# MOSFET_driver.net
KiCad netlist of a schematic drawn in EAGLE
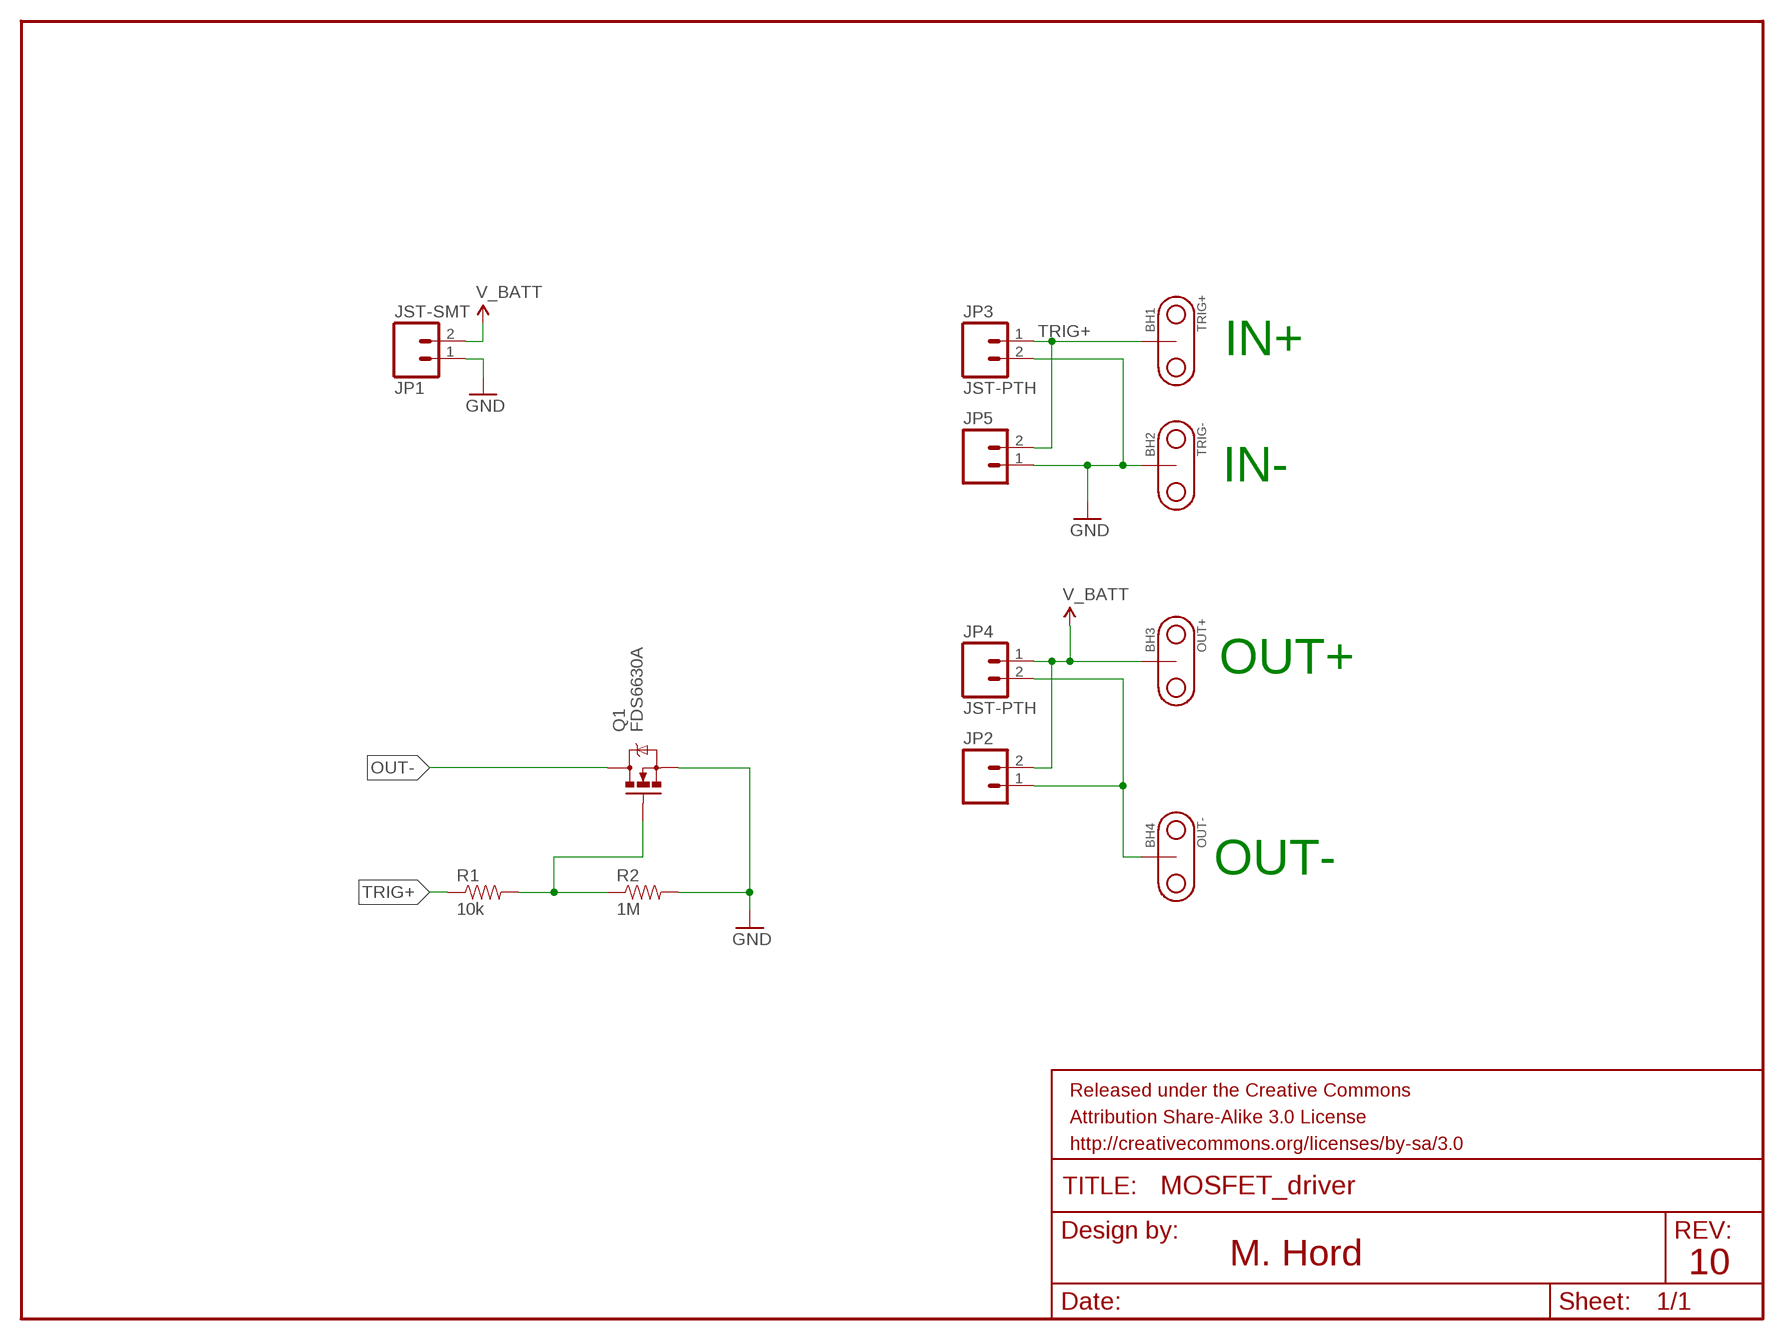
[diagram p0: schematic, sheet 1]

(export (version "E")
  (design (tool "Eeschema 10.0.6"))
  (components
    (comp (ref "BH1")
      (value "TRIG+")
      (footprint "eagle-import:BUTTONHOLE")
      (fields (field (name "NO_PART") "1"))
      (libsource (lib "eagle-import") (part "BUTTONHOLELARGE"))
    )
    (comp (ref "BH2")
      (value "TRIG-")
      (footprint "eagle-import:BUTTONHOLE")
      (fields (field (name "NO_PART") "1"))
      (libsource (lib "eagle-import") (part "BUTTONHOLELARGE"))
    )
    (comp (ref "BH3")
      (value "OUT+")
      (footprint "eagle-import:BUTTONHOLE")
      (fields (field (name "NO_PART") "1"))
      (libsource (lib "eagle-import") (part "BUTTONHOLELARGE"))
    )
    (comp (ref "BH4")
      (value "OUT-")
      (footprint "eagle-import:BUTTONHOLE")
      (fields (field (name "NO_PART") "1"))
      (libsource (lib "eagle-import") (part "BUTTONHOLELARGE"))
    )
    (comp (ref "FRAME1")
      (value "FRAME-LETTER")
      (footprint "eagle-import:CREATIVE_COMMONS")
      (libsource (lib "eagle-import") (part "FRAME-LETTER"))
    )
    (comp (ref "JP1")
      (value "JST-SMT")
      (footprint "eagle-import:JST-2-SMD")
      (fields (field (name "PROD_ID") "CONN-08352"))
      (libsource (lib "eagle-import") (part "M02-JST-2MM-SMT"))
    )
    (comp (ref "JP2")
      (value "M02PTH")
      (footprint "eagle-import:1X02")
      (libsource (lib "eagle-import") (part "M02PTH"))
    )
    (comp (ref "JP3")
      (value "JST-PTH")
      (footprint "eagle-import:JST-2-PTH-NS")
      (fields (field (name "NO_PART") "1"))
      (libsource (lib "eagle-import") (part "M02-JST-2-PTH-NO_SILK"))
    )
    (comp (ref "JP4")
      (value "JST-PTH")
      (footprint "eagle-import:JST-2-PTH-NS")
      (fields (field (name "NO_PART") "1"))
      (libsource (lib "eagle-import") (part "M02-JST-2-PTH-NO_SILK"))
    )
    (comp (ref "JP5")
      (value "M02PTH")
      (footprint "eagle-import:1X02")
      (libsource (lib "eagle-import") (part "M02PTH"))
    )
    (comp (ref "Q1")
      (value "FDS6630A")
      (footprint "eagle-import:SO08")
      (libsource (lib "eagle-import") (part "MOSFET-NCHANNELFDS6630A"))
    )
    (comp (ref "R1")
      (value "10k")
      (footprint "eagle-import:0402-RES")
      (libsource (lib "eagle-import") (part "RESISTOR0402-RES"))
    )
    (comp (ref "R2")
      (value "1M")
      (footprint "eagle-import:0402-RES")
      (libsource (lib "eagle-import") (part "1M-1%"))
    )
  )
  (nets
    (net (code "1") (name "GND") (class "Default")
      (node (ref "BH2") (pin "P$1") (pinfunction "P$1_P$1") (pintype "bidirectional"))
      (node (ref "JP1") (pin "1") (pinfunction "2_1") (pintype "passive"))
      (node (ref "JP3") (pin "2") (pinfunction "2_2") (pintype "passive"))
      (node (ref "JP5") (pin "1") (pinfunction "1_1") (pintype "passive"))
      (node (ref "Q1") (pin "1") (pinfunction "S_1") (pintype "passive"))
      (node (ref "Q1") (pin "2") (pinfunction "S_2") (pintype "passive"))
      (node (ref "Q1") (pin "3") (pinfunction "S_3") (pintype "passive"))
      (node (ref "R2") (pin "2") (pinfunction "2_2") (pintype "passive"))
    )
    (net (code "2") (name "Net-(Q1-G)") (class "Default")
      (node (ref "Q1") (pin "4") (pinfunction "G_4") (pintype "passive"))
      (node (ref "R1") (pin "2") (pinfunction "2_2") (pintype "passive"))
      (node (ref "R2") (pin "1") (pinfunction "1_1") (pintype "passive"))
    )
    (net (code "3") (name "OUT-") (class "Default")
      (node (ref "BH4") (pin "P$1") (pinfunction "P$1_P$1") (pintype "bidirectional"))
      (node (ref "JP2") (pin "1") (pinfunction "1_1") (pintype "passive"))
      (node (ref "JP4") (pin "2") (pinfunction "2_2") (pintype "passive"))
      (node (ref "Q1") (pin "5") (pinfunction "D_5") (pintype "passive"))
      (node (ref "Q1") (pin "6") (pinfunction "D_6") (pintype "passive"))
      (node (ref "Q1") (pin "7") (pinfunction "D_7") (pintype "passive"))
      (node (ref "Q1") (pin "8") (pinfunction "D_8") (pintype "passive"))
    )
    (net (code "4") (name "TRIG+") (class "Default")
      (node (ref "BH1") (pin "P$1") (pinfunction "P$1_P$1") (pintype "bidirectional"))
      (node (ref "JP3") (pin "1") (pinfunction "1_1") (pintype "passive"))
      (node (ref "JP5") (pin "2") (pinfunction "2_2") (pintype "passive"))
      (node (ref "R1") (pin "1") (pinfunction "1_1") (pintype "passive"))
    )
    (net (code "5") (name "V_BATT") (class "Default")
      (node (ref "BH3") (pin "P$1") (pinfunction "P$1_P$1") (pintype "bidirectional"))
      (node (ref "JP1") (pin "2") (pinfunction "1_2") (pintype "passive"))
      (node (ref "JP2") (pin "2") (pinfunction "2_2") (pintype "passive"))
      (node (ref "JP4") (pin "1") (pinfunction "1_1") (pintype "passive"))
    )
  )
)
